# C210_0005_NINA_Module.net
KiCad netlist of a schematic drawn in Altium Designer
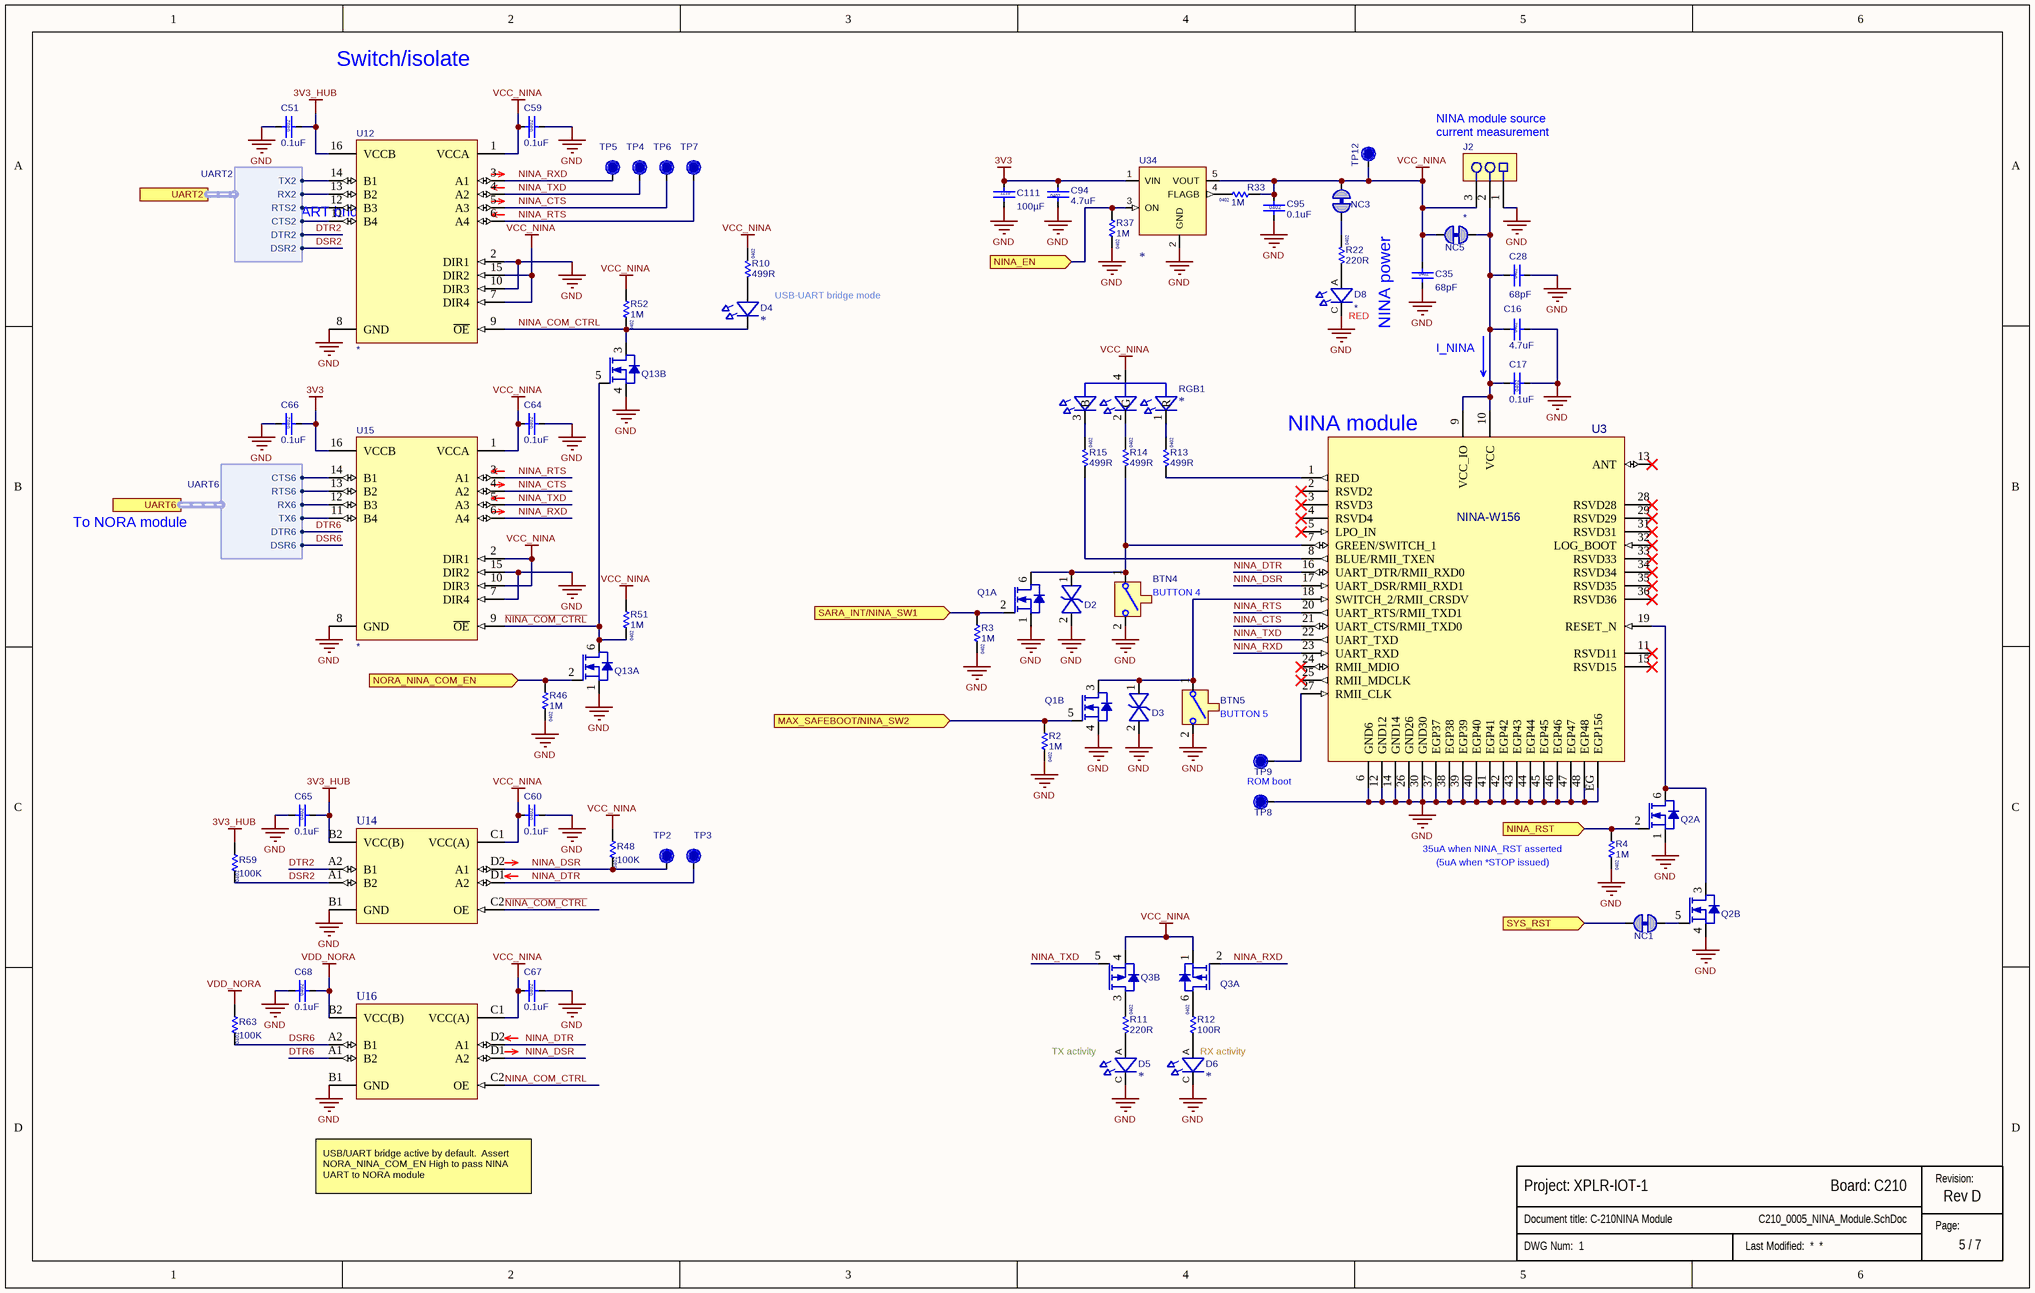
[diagram p0: C210_0005_NINA_Module.SchDoc]

(export (version "E")
  (design (tool "Eeschema 10.0.6"))
  (components
    (comp (ref "BTN4")
      (value "135-00007")
      (footprint "B3U-1000P")
      (description "Button, Momentary SPST-NO, 0.05A, 12V, 3mm x 2.5mm")
      (fields (field (name "VOLTAGE") "12VDC"))
      (libsource (lib "Arena_Parts_DB_Lib") (part "SW_SPST"))
    )
    (comp (ref "BTN5")
      (value "135-00007")
      (footprint "B3U-1000P")
      (description "Button, Momentary SPST-NO, 0.05A, 12V, 3mm x 2.5mm")
      (fields (field (name "VOLTAGE") "12VDC"))
      (libsource (lib "Arena_Parts_DB_Lib") (part "SW_SPST"))
    )
    (comp (ref "C16")
      (value "4.7uF")
      (footprint "Cap 0402 HD")
      (description "Cap, Ceramic 4.7uF 10V 20% X5R 0402")
      (fields
        (field (name "SIZE") "0402")
        (field (name "PART NUMBER") "120-00020")
        (field (name "TOLERANCE") "+/- 20%")
      )
      (libsource (lib "Arena_Parts_DB_Lib") (part "Cap Chip"))
    )
    (comp (ref "C17")
      (value "0.1uF")
      (footprint "Cap 0402 HD")
      (description "Cap, Ceramic 0.1uF 10V 10% X5R 0402")
      (fields
        (field (name "SIZE") "0402")
        (field (name "PART NUMBER") "120-00016")
        (field (name "MANUFACTURER") "Murata Electronics North America")
      )
      (libsource (lib "Arena_Parts_DB_Lib") (part "Cap Chip"))
    )
    (comp (ref "C28")
      (value "68pF")
      (footprint "Cap 0402 HD")
      (description "Cap, Ceramic, 68pF, 50V, 1%, NP0, 0402")
      (fields
        (field (name "SIZE") "0402")
        (field (name "PART NUMBER") "120-00047")
        (field (name "TOLERANCE") "+/- 1%")
      )
      (libsource (lib "Arena_Parts_DB_Lib") (part "Cap Chip"))
    )
    (comp (ref "C35")
      (value "68pF")
      (footprint "Cap 0402 HD")
      (description "Cap, Ceramic, 68pF, 50V, 1%, NP0, 0402")
      (fields
        (field (name "SIZE") "0402")
        (field (name "PART NUMBER") "120-00047")
        (field (name "TOLERANCE") "+/- 1%")
      )
      (libsource (lib "Arena_Parts_DB_Lib") (part "Cap Chip"))
    )
    (comp (ref "C51")
      (value "0.1uF")
      (footprint "Cap 0402 HD")
      (description "Cap, Ceramic 0.1uF 10V 10% X5R 0402")
      (fields
        (field (name "SIZE") "0402")
        (field (name "PART NUMBER") "120-00016")
        (field (name "MANUFACTURER") "Murata Electronics North America")
      )
      (libsource (lib "Arena_Parts_DB_Lib") (part "Cap Chip"))
    )
    (comp (ref "C59")
      (value "0.1uF")
      (footprint "Cap 0402 HD")
      (description "Cap, Ceramic 0.1uF 10V 10% X5R 0402")
      (fields
        (field (name "SIZE") "0402")
        (field (name "PART NUMBER") "120-00016")
        (field (name "MANUFACTURER") "Murata Electronics North America")
      )
      (libsource (lib "Arena_Parts_DB_Lib") (part "Cap Chip"))
    )
    (comp (ref "C60")
      (value "0.1uF")
      (footprint "Cap 0402 HD")
      (description "Cap, Ceramic 0.1uF 10V 10% X5R 0402")
      (fields
        (field (name "SIZE") "0402")
        (field (name "PART NUMBER") "120-00016")
        (field (name "MANUFACTURER") "Murata Electronics North America")
      )
      (libsource (lib "Arena_Parts_DB_Lib") (part "Cap Chip"))
    )
    (comp (ref "C64")
      (value "0.1uF")
      (footprint "Cap 0402 HD")
      (description "Cap, Ceramic 0.1uF 10V 10% X5R 0402")
      (fields
        (field (name "SIZE") "0402")
        (field (name "PART NUMBER") "120-00016")
        (field (name "MANUFACTURER") "Murata Electronics North America")
      )
      (libsource (lib "Arena_Parts_DB_Lib") (part "Cap Chip"))
    )
    (comp (ref "C65")
      (value "0.1uF")
      (footprint "Cap 0402 HD")
      (description "Cap, Ceramic 0.1uF 10V 10% X5R 0402")
      (fields
        (field (name "SIZE") "0402")
        (field (name "PART NUMBER") "120-00016")
        (field (name "MANUFACTURER") "Murata Electronics North America")
      )
      (libsource (lib "Arena_Parts_DB_Lib") (part "Cap Chip"))
    )
    (comp (ref "C66")
      (value "0.1uF")
      (footprint "Cap 0402 HD")
      (description "Cap, Ceramic 0.1uF 10V 10% X5R 0402")
      (fields
        (field (name "SIZE") "0402")
        (field (name "PART NUMBER") "120-00016")
        (field (name "MANUFACTURER") "Murata Electronics North America")
      )
      (libsource (lib "Arena_Parts_DB_Lib") (part "Cap Chip"))
    )
    (comp (ref "C67")
      (value "0.1uF")
      (footprint "Cap 0402 HD")
      (description "Cap, Ceramic 0.1uF 10V 10% X5R 0402")
      (fields
        (field (name "SIZE") "0402")
        (field (name "PART NUMBER") "120-00016")
        (field (name "MANUFACTURER") "Murata Electronics North America")
      )
      (libsource (lib "Arena_Parts_DB_Lib") (part "Cap Chip"))
    )
    (comp (ref "C68")
      (value "0.1uF")
      (footprint "Cap 0402 HD")
      (description "Cap, Ceramic 0.1uF 10V 10% X5R 0402")
      (fields
        (field (name "SIZE") "0402")
        (field (name "PART NUMBER") "120-00016")
        (field (name "MANUFACTURER") "Murata Electronics North America")
      )
      (libsource (lib "Arena_Parts_DB_Lib") (part "Cap Chip"))
    )
    (comp (ref "C94")
      (value "4.7uF")
      (footprint "Cap 0402 HD")
      (description "Cap, Ceramic 4.7uF 10V 20% X5R 0402")
      (fields
        (field (name "SIZE") "0402")
        (field (name "PART NUMBER") "120-00020")
        (field (name "TOLERANCE") "+/- 20%")
      )
      (libsource (lib "Arena_Parts_DB_Lib") (part "Cap Chip"))
    )
    (comp (ref "C95")
      (value "0.1uF")
      (footprint "Cap 0402 HD")
      (description "Cap, Ceramic 0.1uF 10V 10% X5R 0402")
      (fields
        (field (name "SIZE") "0402")
        (field (name "PART NUMBER") "120-00016")
        (field (name "MANUFACTURER") "Murata Electronics North America")
      )
      (libsource (lib "Arena_Parts_DB_Lib") (part "Cap Chip"))
    )
    (comp (ref "C111")
      (value "100µF")
      (footprint "Cap 1210")
      (description "100µF ±20% 10V Ceramic Capacitor X5R 1210 (3225 Metric)")
      (fields
        (field (name "SIZE") "1210")
        (field (name "PART NUMBER") "120-00223")
        (field (name "TOLERANCE") "+/- 20%")
      )
      (libsource (lib "Arena_Parts_DB_Lib") (part "Cap Chip"))
    )
    (comp (ref "D2")
      (value "110-00041")
      (footprint "SOD-523_ALT")
      (description "Diode TVS 5VWM BiDIR SOD523")
      (fields (field (name "VOLTAGE") "5VWM"))
      (libsource (lib "Arena_Parts_DB_Lib") (part "Diode_TVS"))
    )
    (comp (ref "D3")
      (value "110-00041")
      (footprint "SOD-523_ALT")
      (description "Diode TVS 5VWM BiDIR SOD523")
      (fields (field (name "VOLTAGE") "5VWM"))
      (libsource (lib "Arena_Parts_DB_Lib") (part "Diode_TVS"))
    )
    (comp (ref "D4")
      (value "115-00023")
      (footprint "LED-0603")
      (description "LED BLUE DIFFUSED 0603 SMD")
      (fields (field (name "COLOR") "*") (field (name "VOLTAGE") "None"))
      (libsource (lib "Arena_Parts_DB_Lib") (part "LED_BASE"))
    )
    (comp (ref "D5")
      (value "115-00019")
      (footprint "LTST-C190KGKT")
      (description "DIODE, LED, SMT, GREEN, CLEAR LENS, 2.0V 20mA, 0603")
      (fields (field (name "VOLTAGE") "2.0V") (field (name "COLOR") "*"))
      (libsource (lib "LTST-C190KGKT") (part "LTST-C190KGKT"))
    )
    (comp (ref "D6")
      (value "LTST-C190YKT")
      (footprint "LTST-C190YKT")
      (description "DIODE, LED, SMT, YELLOW, CLEAR LENS, 2.1V 10mA, 0603")
      (fields (field (name "VOLTAGE") "2.1V") (field (name "COLOR") "*"))
      (libsource (lib "LTST-C190YKT") (part "LTST-C190YKT"))
    )
    (comp (ref "D8")
      (value "LTST-C190EKT")
      (footprint "LTST-C190EKT")
      (description "DIODE, LED, SMT, Red, CLEAR LENS, 2.0V 10mA, 0603")
      (fields (field (name "VOLTAGE") "2.0V") (field (name "COLOR") "*"))
      (libsource (lib "LTST-C190EKT") (part "LTST-C190EKT"))
    )
    (comp (ref "J2")
      (value "130-00105")
      (footprint "HDR-0.1P-3Pin-1Row-SMT")
      (description "Header, 0.100\" Pitch, 3 Pin, Vertical SMT, Black")
      (fields (field (name "MANUFACTURER P/N") "*") (field (name "VOLTAGE") "None"))
      (libsource (lib "Arena_Parts_DB_Lib") (part "CON-3Pin_1Row"))
    )
    (comp (ref "NC1")
      (value "Solderbridge-ShortDNP")
      (footprint "Solderbridge-Short")
      (description "Solderbridge-Short")
      (fields (field (name "ADDED BY") "Paul B"))
      (libsource (lib "PCB_Misc") (part "Solderbridge-Short"))
    )
    (comp (ref "NC3")
      (value "Solderbridge-ShortDNP")
      (footprint "Solderbridge-Short")
      (description "Solderbridge-Short")
      (fields (field (name "ADDED BY") "Paul B"))
      (libsource (lib "") (part "Solderbridge-Short_1"))
    )
    (comp (ref "NC5")
      (value "Solderbridge-ShortDNP")
      (footprint "Solderbridge-Short")
      (description "Solderbridge-Short")
      (fields (field (name "ADDED BY") "Paul B"))
      (libsource (lib "PCB_Misc") (part "Solderbridge-Short"))
    )
    (comp (ref "Q1")
      (value "140-00016")
      (footprint "SOT-563")
      (description "MOSFET 2N-CH 20V 0.8A, SOT-563")
      (fields (field (name "VOLTAGE") "20V"))
      (libsource (lib "Arena_Parts_DB_Lib") (part "MOSFET-N-Dual"))
    )
    (comp (ref "Q2")
      (value "140-00016")
      (footprint "SOT-563")
      (description "MOSFET 2N-CH 20V 0.8A, SOT-563")
      (fields (field (name "VOLTAGE") "20V"))
      (libsource (lib "Arena_Parts_DB_Lib") (part "MOSFET-N-Dual"))
    )
    (comp (ref "Q3")
      (value "FDY2000PZ")
      (footprint "FDY2000PZ")
      (description "MOSFET DUAL P-CH 20V SOT-563, -350mA")
      (fields (field (name "VOLTAGE") "20V"))
      (libsource (lib "FDY2000PZ") (part "MOSFET-Dual-P_Chan"))
    )
    (comp (ref "Q13")
      (value "140-00016")
      (footprint "SOT-563")
      (description "MOSFET 2N-CH 20V 0.8A, SOT-563")
      (fields (field (name "VOLTAGE") "20V"))
      (libsource (lib "Arena_Parts_DB_Lib") (part "MOSFET-N-Dual"))
    )
    (comp (ref "R2")
      (value "1M")
      (footprint "RES 0402 HD")
      (description "Resistor 1M ohm 1%, 1/16W, 0402")
      (fields
        (field (name "SIZE") "0402")
        (field (name "PART NUMBER") "180-00054")
        (field (name "POWER") "1/16W")
      )
      (libsource (lib "Arena_Parts_DB_Lib") (part "Res sm"))
    )
    (comp (ref "R3")
      (value "1M")
      (footprint "RES 0402 HD")
      (description "Resistor 1M ohm 1%, 1/16W, 0402")
      (fields
        (field (name "SIZE") "0402")
        (field (name "PART NUMBER") "180-00054")
        (field (name "POWER") "1/16W")
      )
      (libsource (lib "Arena_Parts_DB_Lib") (part "Res sm"))
    )
    (comp (ref "R4")
      (value "1M")
      (footprint "RES 0402 HD")
      (description "Resistor 1M ohm 1%, 1/16W, 0402")
      (fields
        (field (name "SIZE") "0402")
        (field (name "PART NUMBER") "180-00054")
        (field (name "POWER") "1/16W")
      )
      (libsource (lib "Arena_Parts_DB_Lib") (part "Res sm"))
    )
    (comp (ref "R10")
      (value "499R")
      (footprint "RES 0402 HD")
      (description "Resistor, 499ohm, 1%, 1/16W, 0402")
      (fields
        (field (name "SIZE") "0402")
        (field (name "PART NUMBER") "180-00031")
        (field (name "MANUFACTURER") "Rohm Semiconductor")
      )
      (libsource (lib "Arena_Parts_DB_Lib") (part "Res sm"))
    )
    (comp (ref "R11")
      (value "220R")
      (footprint "RES 0402 HD")
      (description "Resistor, 220ohm, 5%, 1/16W, 0402.")
      (fields
        (field (name "SIZE") "0402")
        (field (name "PART NUMBER") "180-00098")
        (field (name "MANUFACTURER") "Panasonic Electronic Components")
      )
      (libsource (lib "Arena_Parts_DB_Lib") (part "Res sm"))
    )
    (comp (ref "R12")
      (value "100R")
      (footprint "RES 0402 HD")
      (description "Resistor, 100ohm, 1%, 1/16W, 0402.")
      (fields
        (field (name "SIZE") "0402")
        (field (name "PART NUMBER") "180-00051")
        (field (name "POWER") "1/16W")
      )
      (libsource (lib "Arena_Parts_DB_Lib") (part "Res sm"))
    )
    (comp (ref "R13")
      (value "499R")
      (footprint "RES 0402 HD")
      (description "Resistor, 499ohm, 1%, 1/16W, 0402")
      (fields
        (field (name "SIZE") "0402")
        (field (name "PART NUMBER") "180-00031")
        (field (name "MANUFACTURER") "Rohm Semiconductor")
      )
      (libsource (lib "Arena_Parts_DB_Lib") (part "Res sm"))
    )
    (comp (ref "R14")
      (value "499R")
      (footprint "RES 0402 HD")
      (description "Resistor, 499ohm, 1%, 1/16W, 0402")
      (fields
        (field (name "SIZE") "0402")
        (field (name "PART NUMBER") "180-00031")
        (field (name "MANUFACTURER") "Rohm Semiconductor")
      )
      (libsource (lib "Arena_Parts_DB_Lib") (part "Res sm"))
    )
    (comp (ref "R15")
      (value "499R")
      (footprint "RES 0402 HD")
      (description "Resistor, 499ohm, 1%, 1/16W, 0402")
      (fields
        (field (name "SIZE") "0402")
        (field (name "PART NUMBER") "180-00031")
        (field (name "MANUFACTURER") "Rohm Semiconductor")
      )
      (libsource (lib "Arena_Parts_DB_Lib") (part "Res sm"))
    )
    (comp (ref "R22")
      (value "220R")
      (footprint "RES 0402 HD")
      (description "Resistor, 220ohm, 5%, 1/16W, 0402.")
      (fields
        (field (name "SIZE") "0402")
        (field (name "PART NUMBER") "180-00098")
        (field (name "MANUFACTURER") "Panasonic Electronic Components")
      )
      (libsource (lib "Arena_Parts_DB_Lib") (part "Res sm"))
    )
    (comp (ref "R33")
      (value "1M")
      (footprint "RES 0402 HD")
      (description "Resistor 1M ohm 1%, 1/16W, 0402")
      (fields
        (field (name "SIZE") "0402")
        (field (name "PART NUMBER") "180-00054")
        (field (name "POWER") "1/16W")
      )
      (libsource (lib "Arena_Parts_DB_Lib") (part "Res sm"))
    )
    (comp (ref "R37")
      (value "1M")
      (footprint "RES 0402 HD")
      (description "Resistor 1M ohm 1%, 1/16W, 0402")
      (fields
        (field (name "SIZE") "0402")
        (field (name "PART NUMBER") "180-00054")
        (field (name "POWER") "1/16W")
      )
      (libsource (lib "Arena_Parts_DB_Lib") (part "Res sm"))
    )
    (comp (ref "R46")
      (value "1M")
      (footprint "RES 0402 HD")
      (description "Resistor 1M ohm 1%, 1/16W, 0402")
      (fields
        (field (name "SIZE") "0402")
        (field (name "PART NUMBER") "180-00054")
        (field (name "POWER") "1/16W")
      )
      (libsource (lib "Arena_Parts_DB_Lib") (part "Res sm"))
    )
    (comp (ref "R48")
      (value "100K")
      (footprint "RES 0402 HD")
      (description "Resistor 100K ohm 1% 1/16W, 0402")
      (fields
        (field (name "SIZE") "0402")
        (field (name "PART NUMBER") "180-00093")
        (field (name "POWER") "1/16W")
      )
      (libsource (lib "Arena_Parts_DB_Lib") (part "Res sm"))
    )
    (comp (ref "R51")
      (value "1M")
      (footprint "RES 0402 HD")
      (description "Resistor 1M ohm 1%, 1/16W, 0402")
      (fields
        (field (name "SIZE") "0402")
        (field (name "PART NUMBER") "180-00054")
        (field (name "POWER") "1/16W")
      )
      (libsource (lib "Arena_Parts_DB_Lib") (part "Res sm"))
    )
    (comp (ref "R52")
      (value "1M")
      (footprint "RES 0402 HD")
      (description "Resistor 1M ohm 1%, 1/16W, 0402")
      (fields
        (field (name "SIZE") "0402")
        (field (name "PART NUMBER") "180-00054")
        (field (name "POWER") "1/16W")
      )
      (libsource (lib "Arena_Parts_DB_Lib") (part "Res sm"))
    )
    (comp (ref "R59")
      (value "100K")
      (footprint "RES 0402 HD")
      (description "Resistor 100K ohm 1% 1/16W, 0402")
      (fields
        (field (name "SIZE") "0402")
        (field (name "PART NUMBER") "180-00093")
        (field (name "POWER") "1/16W")
      )
      (libsource (lib "Arena_Parts_DB_Lib") (part "Res sm"))
    )
    (comp (ref "R63")
      (value "100K")
      (footprint "RES 0402 HD")
      (description "Resistor 100K ohm 1% 1/16W, 0402")
      (fields
        (field (name "SIZE") "0402")
        (field (name "PART NUMBER") "180-00093")
        (field (name "POWER") "1/16W")
      )
      (libsource (lib "Arena_Parts_DB_Lib") (part "Res sm"))
    )
    (comp (ref "RGB1")
      (value "115-00026")
      (footprint "LED_1616")
      (description "LED RGB SMT 0606")
      (fields (field (name "COLOR") "*") (field (name "VOLTAGE") "None"))
      (libsource (lib "Arena_Parts_DB_Lib") (part "LED_RGB_CA_4"))
    )
    (comp (ref "TP2")
      (value "TP")
      (footprint "TP12R")
      (description "Testpoint, Round 1.0mm Dia")
      (fields
        (field (name "PART NUMBER") "TP10R")
        (field (name "ADDED BY") "Jeremy D")
        (field (name "CHECKED BY") "Paul B")
      )
      (libsource (lib "PCB_Misc") (part "TP_R"))
    )
    (comp (ref "TP3")
      (value "TP")
      (footprint "TP12R")
      (description "Testpoint, Round 1.0mm Dia")
      (fields
        (field (name "PART NUMBER") "TP10R")
        (field (name "ADDED BY") "Jeremy D")
        (field (name "CHECKED BY") "Paul B")
      )
      (libsource (lib "PCB_Misc") (part "TP_R"))
    )
    (comp (ref "TP4")
      (value "TP")
      (footprint "TP12R")
      (description "Testpoint, Round 1.0mm Dia")
      (fields
        (field (name "PART NUMBER") "TP10R")
        (field (name "ADDED BY") "Jeremy D")
        (field (name "CHECKED BY") "Paul B")
      )
      (libsource (lib "PCB_Misc") (part "TP_R"))
    )
    (comp (ref "TP5")
      (value "TP")
      (footprint "TP12R")
      (description "Testpoint, Round 1.0mm Dia")
      (fields
        (field (name "PART NUMBER") "TP10R")
        (field (name "ADDED BY") "Jeremy D")
        (field (name "CHECKED BY") "Paul B")
      )
      (libsource (lib "PCB_Misc") (part "TP_R"))
    )
    (comp (ref "TP6")
      (value "TP")
      (footprint "TP12R")
      (description "Testpoint, Round 1.0mm Dia")
      (fields
        (field (name "PART NUMBER") "TP10R")
        (field (name "ADDED BY") "Jeremy D")
        (field (name "CHECKED BY") "Paul B")
      )
      (libsource (lib "PCB_Misc") (part "TP_R"))
    )
    (comp (ref "TP7")
      (value "TP")
      (footprint "TP12R")
      (description "Testpoint, Round 1.0mm Dia")
      (fields
        (field (name "PART NUMBER") "TP10R")
        (field (name "ADDED BY") "Jeremy D")
        (field (name "CHECKED BY") "Paul B")
      )
      (libsource (lib "PCB_Misc") (part "TP_R"))
    )
    (comp (ref "TP8")
      (value "TP")
      (footprint "TP12R")
      (description "Testpoint, Round 1.0mm Dia")
      (fields
        (field (name "PART NUMBER") "TP10R")
        (field (name "ADDED BY") "Jeremy D")
        (field (name "CHECKED BY") "Paul B")
      )
      (libsource (lib "PCB_Misc") (part "TP_R"))
    )
    (comp (ref "TP9")
      (value "TP")
      (footprint "TP12R")
      (description "Testpoint, Round 1.0mm Dia")
      (fields
        (field (name "PART NUMBER") "TP10R")
        (field (name "ADDED BY") "Jeremy D")
        (field (name "CHECKED BY") "Paul B")
      )
      (libsource (lib "PCB_Misc") (part "TP_R"))
    )
    (comp (ref "TP12")
      (value "TP")
      (footprint "TP12R")
      (description "Testpoint, Round 1.0mm Dia")
      (fields
        (field (name "PART NUMBER") "TP10R")
        (field (name "ADDED BY") "Jeremy D")
        (field (name "CHECKED BY") "Paul B")
      )
      (libsource (lib "PCB_Misc") (part "TP_R"))
    )
    (comp (ref "U3")
      (value "NINA-W156")
      (footprint "NINA_LGA48R_1400X1000X223_PCB")
      (description "u-blox NINA-W156 WiFi, Bluetooth dual-mode module")
      (fields (field (name "MANUFACTURER") "u-blox"))
      (libsource (lib "ubloxLib") (part "NINA-W156"))
    )
    (comp (ref "U12")
      (value "225-00011")
      (footprint "QFN0.5P2x6-16Pin_W-Pad")
      (description "Voltage Level Translator Bidirectional 1 Circuit 4 Channel 380Mbps 16-DHVQFN (2.5x3.5)")
      (fields (field (name "MANUFACTURER P/N") "*") (field (name "VOLTAGE") "3.6V"))
      (libsource (lib "Arena_Parts_DB_Lib") (part "74AVC4TD245"))
    )
    (comp (ref "U14")
      (value "TXS0102YZP")
      (footprint "TXS0102YZP")
      (description "IC, SMT, LEVEL TRANSLATOR, DUAL, BIDIRECTIONAL, DSBGA-8 1.9mmX0.9mm")
      (libsource (lib "TXS0102YZP") (part "TXS0102YZP"))
    )
    (comp (ref "U15")
      (value "225-00011")
      (footprint "QFN0.5P2x6-16Pin_W-Pad")
      (description "Voltage Level Translator Bidirectional 1 Circuit 4 Channel 380Mbps 16-DHVQFN (2.5x3.5)")
      (fields (field (name "MANUFACTURER P/N") "*") (field (name "VOLTAGE") "3.6V"))
      (libsource (lib "Arena_Parts_DB_Lib") (part "74AVC4TD245"))
    )
    (comp (ref "U16")
      (value "TXS0102YZP")
      (footprint "TXS0102YZP")
      (description "IC, SMT, LEVEL TRANSLATOR, DUAL, BIDIRECTIONAL, DSBGA-8 1.9mmX0.9mm")
      (libsource (lib "TXS0102YZP") (part "TXS0102YZP"))
    )
    (comp (ref "U34")
      (value "~")
      (footprint "SOT-23-5_2")
      (description "Load Switch, 400mA, 1.8-5.5V, Active High Enable, SOT-23-5")
      (fields (field (name "VOLTAGE") "5.5V") (field (name "MANUFACTURER P/N") "*"))
      (libsource (lib "FPF2104") (part "FPF2104"))
    )
  )
  (nets
    (net (code "3") (name "/CTS2") (class "Default")
      (node (ref "U12") (pin "11") (pinfunction "B4_11") (pintype "bidirectional"))
    )
    (net (code "4") (name "/CTS6") (class "Default")
      (node (ref "U15") (pin "14") (pinfunction "B1_14") (pintype "bidirectional"))
    )
    (net (code "5") (name "/DSR2") (class "Default")
      (node (ref "R59") (pin "2") (pinfunction "2_2") (pintype "passive"))
      (node (ref "U14") (pin "A1") (pinfunction "B2_A1") (pintype "bidirectional"))
    )
    (net (code "6") (name "/DSR6") (class "Default")
      (node (ref "R63") (pin "2") (pinfunction "2_2") (pintype "passive"))
      (node (ref "U16") (pin "A2") (pinfunction "B1_A2") (pintype "bidirectional"))
    )
    (net (code "7") (name "/DTR2") (class "Default")
      (node (ref "U14") (pin "A2") (pinfunction "B1_A2") (pintype "bidirectional"))
    )
    (net (code "8") (name "/DTR6") (class "Default")
      (node (ref "U16") (pin "A1") (pinfunction "B2_A1") (pintype "bidirectional"))
    )
    (net (code "9") (name "/MAX_SAFEBOOT{slash}NINA_SW2") (class "Default")
      (node (ref "Q1") (pin "5") (pinfunction "G2_5") (pintype "passive"))
      (node (ref "R2") (pin "1") (pinfunction "1_1") (pintype "passive"))
    )
    (net (code "10") (name "/NINA_COM_CTRL") (class "Default")
      (node (ref "D4") (pin "1") (pinfunction "C_1") (pintype "passive"))
      (node (ref "Q13") (pin "3") (pinfunction "D2_3") (pintype "passive"))
      (node (ref "R52") (pin "2") (pinfunction "2_2") (pintype "passive"))
      (node (ref "U12") (pin "9") (pinfunction "~{OE}_9") (pintype "input"))
      (node (ref "U16") (pin "C2") (pinfunction "OE_C2") (pintype "input"))
    )
    (net (code "11") (name "/NINA_CTS") (class "Default")
      (node (ref "TP6") (pin "1") (pintype "passive"))
      (node (ref "U12") (pin "5") (pinfunction "A3_5") (pintype "bidirectional"))
      (node (ref "U15") (pin "4") (pinfunction "A2_4") (pintype "bidirectional"))
      (node (ref "U3") (pin "21") (pinfunction "UART_CTS/RMII_TXD0_21") (pintype "bidirectional"))
    )
    (net (code "12") (name "/NINA_DSR") (class "Default")
      (node (ref "R48") (pin "2") (pinfunction "2_2") (pintype "passive"))
      (node (ref "TP2") (pin "1") (pintype "passive"))
      (node (ref "U14") (pin "D2") (pinfunction "A1_D2") (pintype "bidirectional"))
      (node (ref "U16") (pin "D1") (pinfunction "A2_D1") (pintype "bidirectional"))
      (node (ref "U3") (pin "17") (pinfunction "UART_DSR/RMII_RXD1_17") (pintype "input"))
    )
    (net (code "13") (name "/NINA_DTR") (class "Default")
      (node (ref "TP3") (pin "1") (pintype "passive"))
      (node (ref "U14") (pin "D1") (pinfunction "A2_D1") (pintype "bidirectional"))
      (node (ref "U16") (pin "D2") (pinfunction "A1_D2") (pintype "bidirectional"))
      (node (ref "U3") (pin "16") (pinfunction "UART_DTR/RMII_RXD0_16") (pintype "bidirectional"))
    )
    (net (code "14") (name "/NINA_EN") (class "Default")
      (node (ref "R37") (pin "1") (pinfunction "1_1") (pintype "passive"))
      (node (ref "U34") (pin "3") (pinfunction "ON_3") (pintype "input"))
    )
    (net (code "15") (name "/NINA_RST") (class "Default")
      (node (ref "Q2") (pin "2") (pinfunction "G1_2") (pintype "passive"))
      (node (ref "R4") (pin "1") (pinfunction "1_1") (pintype "passive"))
    )
    (net (code "16") (name "/NINA_RTS") (class "Default")
      (node (ref "TP7") (pin "1") (pintype "passive"))
      (node (ref "U12") (pin "6") (pinfunction "A4_6") (pintype "bidirectional"))
      (node (ref "U15") (pin "3") (pinfunction "A1_3") (pintype "bidirectional"))
      (node (ref "U3") (pin "20") (pinfunction "UART_RTS/RMII_TXD1_20") (pintype "output"))
    )
    (net (code "17") (name "/NINA_RXD") (class "Default")
      (node (ref "Q3") (pin "2") (pinfunction "G1_2") (pintype "passive"))
      (node (ref "TP5") (pin "1") (pintype "passive"))
      (node (ref "U12") (pin "3") (pinfunction "A1_3") (pintype "bidirectional"))
      (node (ref "U15") (pin "6") (pinfunction "A4_6") (pintype "bidirectional"))
      (node (ref "U3") (pin "23") (pinfunction "UART_RXD_23") (pintype "input"))
    )
    (net (code "18") (name "/NINA_TXD") (class "Default")
      (node (ref "Q3") (pin "5") (pinfunction "G2_5") (pintype "passive"))
      (node (ref "TP4") (pin "1") (pintype "passive"))
      (node (ref "U12") (pin "4") (pinfunction "A2_4") (pintype "bidirectional"))
      (node (ref "U15") (pin "5") (pinfunction "A3_5") (pintype "bidirectional"))
      (node (ref "U3") (pin "22") (pinfunction "UART_TXD_22") (pintype "output"))
    )
    (net (code "19") (name "/NORA_NINA_COM_EN") (class "Default")
      (node (ref "Q13") (pin "2") (pinfunction "G1_2") (pintype "passive"))
      (node (ref "R46") (pin "1") (pinfunction "1_1") (pintype "passive"))
    )
    (net (code "20") (name "/RTS2") (class "Default")
      (node (ref "U12") (pin "12") (pinfunction "B3_12") (pintype "bidirectional"))
    )
    (net (code "21") (name "/RTS6") (class "Default")
      (node (ref "U15") (pin "13") (pinfunction "B2_13") (pintype "bidirectional"))
    )
    (net (code "22") (name "/RX2") (class "Default")
      (node (ref "U12") (pin "13") (pinfunction "B2_13") (pintype "bidirectional"))
    )
    (net (code "23") (name "/RX6") (class "Default")
      (node (ref "U15") (pin "12") (pinfunction "B3_12") (pintype "bidirectional"))
    )
    (net (code "24") (name "/SARA_INT{slash}NINA_SW1") (class "Default")
      (node (ref "Q1") (pin "2") (pinfunction "G1_2") (pintype "passive"))
      (node (ref "R3") (pin "1") (pinfunction "1_1") (pintype "passive"))
    )
    (net (code "25") (name "/SYS_RST") (class "Default")
      (node (ref "NC1") (pin "2") (pinfunction "2_2") (pintype "passive"))
    )
    (net (code "26") (name "/TX2") (class "Default")
      (node (ref "U12") (pin "14") (pinfunction "B1_14") (pintype "bidirectional"))
    )
    (net (code "27") (name "/TX6") (class "Default")
      (node (ref "U15") (pin "11") (pinfunction "B4_11") (pintype "bidirectional"))
    )
    (net (code "30") (name "/~{NINA_COM_CTRL}") (class "Default")
      (node (ref "Q13") (pin "5") (pinfunction "G2_5") (pintype "passive"))
      (node (ref "Q13") (pin "6") (pinfunction "D1_6") (pintype "passive"))
      (node (ref "R51") (pin "2") (pinfunction "2_2") (pintype "passive"))
      (node (ref "U14") (pin "C2") (pinfunction "OE_C2") (pintype "input"))
      (node (ref "U15") (pin "9") (pinfunction "~{OE}_9") (pintype "input"))
    )
    (net (code "31") (name "3V3") (class "Default")
      (node (ref "C111") (pin "1") (pinfunction "1_1") (pintype "passive"))
      (node (ref "C66") (pin "2") (pinfunction "2_2") (pintype "passive"))
      (node (ref "C94") (pin "2") (pinfunction "2_2") (pintype "passive"))
      (node (ref "U15") (pin "16") (pinfunction "VCCB_16") (pintype "power_in"))
      (node (ref "U34") (pin "1") (pinfunction "VIN_1") (pintype "power_in"))
    )
    (net (code "32") (name "3V3_HUB") (class "Default")
      (node (ref "C51") (pin "2") (pinfunction "2_2") (pintype "passive"))
      (node (ref "C65") (pin "2") (pinfunction "2_2") (pintype "passive"))
      (node (ref "R59") (pin "1") (pinfunction "1_1") (pintype "passive"))
      (node (ref "U12") (pin "16") (pinfunction "VCCB_16") (pintype "power_in"))
      (node (ref "U14") (pin "B2") (pinfunction "VCC(B)_B2") (pintype "power_in"))
    )
    (net (code "33") (name "GND") (class "Default")
      (node (ref "BTN4") (pin "2") (pinfunction "2_2") (pintype "passive"))
      (node (ref "BTN5") (pin "2") (pinfunction "2_2") (pintype "passive"))
      (node (ref "C111") (pin "2") (pinfunction "2_2") (pintype "passive"))
      (node (ref "C16") (pin "2") (pinfunction "2_2") (pintype "passive"))
      (node (ref "C17") (pin "1") (pinfunction "1_1") (pintype "passive"))
      (node (ref "C28") (pin "2") (pinfunction "2_2") (pintype "passive"))
      (node (ref "C35") (pin "2") (pinfunction "2_2") (pintype "passive"))
      (node (ref "C51") (pin "1") (pinfunction "1_1") (pintype "passive"))
      (node (ref "C59") (pin "2") (pinfunction "2_2") (pintype "passive"))
      (node (ref "C60") (pin "2") (pinfunction "2_2") (pintype "passive"))
      (node (ref "C64") (pin "2") (pinfunction "2_2") (pintype "passive"))
      (node (ref "C65") (pin "1") (pinfunction "1_1") (pintype "passive"))
      (node (ref "C66") (pin "1") (pinfunction "1_1") (pintype "passive"))
      (node (ref "C67") (pin "2") (pinfunction "2_2") (pintype "passive"))
      (node (ref "C68") (pin "1") (pinfunction "1_1") (pintype "passive"))
      (node (ref "C94") (pin "1") (pinfunction "1_1") (pintype "passive"))
      (node (ref "C95") (pin "2") (pinfunction "2_2") (pintype "passive"))
      (node (ref "D2") (pin "2") (pintype "passive"))
      (node (ref "D3") (pin "2") (pintype "passive"))
      (node (ref "D5") (pin "C") (pinfunction "Cathode_C") (pintype "passive"))
      (node (ref "D6") (pin "C") (pinfunction "Cathode_C") (pintype "passive"))
      (node (ref "D8") (pin "C") (pinfunction "Cathode_C") (pintype "passive"))
      (node (ref "J2") (pin "1") (pinfunction "1_1") (pintype "passive"))
      (node (ref "Q1") (pin "1") (pinfunction "S1_1") (pintype "passive"))
      (node (ref "Q1") (pin "4") (pinfunction "S2_4") (pintype "passive"))
      (node (ref "Q13") (pin "1") (pinfunction "S1_1") (pintype "passive"))
      (node (ref "Q13") (pin "4") (pinfunction "S2_4") (pintype "passive"))
      (node (ref "Q2") (pin "1") (pinfunction "S1_1") (pintype "passive"))
      (node (ref "Q2") (pin "4") (pinfunction "S2_4") (pintype "passive"))
      (node (ref "R2") (pin "2") (pinfunction "2_2") (pintype "passive"))
      (node (ref "R3") (pin "2") (pinfunction "2_2") (pintype "passive"))
      (node (ref "R37") (pin "2") (pinfunction "2_2") (pintype "passive"))
      (node (ref "R4") (pin "2") (pinfunction "2_2") (pintype "passive"))
      (node (ref "R46") (pin "2") (pinfunction "2_2") (pintype "passive"))
      (node (ref "TP8") (pin "1") (pintype "passive"))
      (node (ref "U12") (pin "10") (pinfunction "DIR3_10") (pintype "input"))
      (node (ref "U12") (pin "2") (pinfunction "DIR1_2") (pintype "input"))
      (node (ref "U12") (pin "8") (pinfunction "GND_8") (pintype "power_in"))
      (node (ref "U14") (pin "B1") (pinfunction "GND_B1") (pintype "power_in"))
      (node (ref "U15") (pin "15") (pinfunction "DIR2_15") (pintype "input"))
      (node (ref "U15") (pin "7") (pinfunction "DIR4_7") (pintype "input"))
      (node (ref "U15") (pin "8") (pinfunction "GND_8") (pintype "power_in"))
      (node (ref "U16") (pin "B1") (pinfunction "GND_B1") (pintype "power_in"))
      (node (ref "U3") (pin "12") (pinfunction "GND12_12") (pintype "power_in"))
      (node (ref "U3") (pin "14") (pinfunction "GND14_14") (pintype "power_in"))
      (node (ref "U3") (pin "26") (pinfunction "GND26_26") (pintype "power_in"))
      (node (ref "U3") (pin "30") (pinfunction "GND30_30") (pintype "power_in"))
      (node (ref "U3") (pin "37") (pinfunction "EGP37_37") (pintype "power_in"))
      (node (ref "U3") (pin "38") (pinfunction "EGP38_38") (pintype "power_in"))
      (node (ref "U3") (pin "39") (pinfunction "EGP39_39") (pintype "power_in"))
      (node (ref "U3") (pin "40") (pinfunction "EGP40_40") (pintype "power_in"))
      (node (ref "U3") (pin "41") (pinfunction "EGP41_41") (pintype "power_in"))
      (node (ref "U3") (pin "42") (pinfunction "EGP42_42") (pintype "power_in"))
      (node (ref "U3") (pin "43") (pinfunction "EGP43_43") (pintype "power_in"))
      (node (ref "U3") (pin "44") (pinfunction "EGP44_44") (pintype "power_in"))
      (node (ref "U3") (pin "45") (pinfunction "EGP45_45") (pintype "power_in"))
      (node (ref "U3") (pin "46") (pinfunction "EGP46_46") (pintype "power_in"))
      (node (ref "U3") (pin "47") (pinfunction "EGP47_47") (pintype "power_in"))
      (node (ref "U3") (pin "48") (pinfunction "EGP48_48") (pintype "power_in"))
      (node (ref "U3") (pin "6") (pinfunction "GND6_6") (pintype "power_in"))
      (node (ref "U3") (pin "EG") (pinfunction "EGP156_EG") (pintype "power_in"))
      (node (ref "U34") (pin "2") (pinfunction "GND_2") (pintype "power_in"))
    )
    (net (code "34") (name "Net-(D4-A)") (class "Default")
      (node (ref "D4") (pin "2") (pinfunction "A_2") (pintype "passive"))
      (node (ref "R10") (pin "1") (pinfunction "1_1") (pintype "passive"))
    )
    (net (code "35") (name "Net-(D5-Anode)") (class "Default")
      (node (ref "D5") (pin "A") (pinfunction "Anode_A") (pintype "passive"))
      (node (ref "R11") (pin "1") (pinfunction "1_1") (pintype "passive"))
    )
    (net (code "36") (name "Net-(D6-Anode)") (class "Default")
      (node (ref "D6") (pin "A") (pinfunction "Anode_A") (pintype "passive"))
      (node (ref "R12") (pin "1") (pinfunction "1_1") (pintype "passive"))
    )
    (net (code "37") (name "Net-(D8-Anode)") (class "Default")
      (node (ref "D8") (pin "A") (pinfunction "Anode_A") (pintype "passive"))
      (node (ref "R22") (pin "1") (pinfunction "1_1") (pintype "passive"))
    )
    (net (code "38") (name "Net-(NC3-Pad2)") (class "Default")
      (node (ref "NC3") (pin "2") (pinfunction "2_2") (pintype "passive"))
      (node (ref "R22") (pin "2") (pinfunction "2_2") (pintype "passive"))
    )
    (net (code "39") (name "Net-(Q1A-D1)") (class "Default")
      (node (ref "BTN4") (pin "1") (pinfunction "1_1") (pintype "passive"))
      (node (ref "D2") (pin "1") (pintype "passive"))
      (node (ref "Q1") (pin "6") (pinfunction "D1_6") (pintype "passive"))
      (node (ref "R14") (pin "1") (pinfunction "1_1") (pintype "passive"))
      (node (ref "U3") (pin "7") (pinfunction "GREEN/SWITCH_1_7") (pintype "bidirectional"))
    )
    (net (code "40") (name "Net-(Q1B-D2)") (class "Default")
      (node (ref "BTN5") (pin "1") (pinfunction "1_1") (pintype "passive"))
      (node (ref "D3") (pin "1") (pintype "passive"))
      (node (ref "Q1") (pin "3") (pinfunction "D2_3") (pintype "passive"))
      (node (ref "U3") (pin "18") (pinfunction "SWITCH_2/RMII_CRSDV_18") (pintype "input"))
    )
    (net (code "41") (name "Net-(Q2A-D1)") (class "Default")
      (node (ref "Q2") (pin "3") (pinfunction "D2_3") (pintype "passive"))
      (node (ref "Q2") (pin "6") (pinfunction "D1_6") (pintype "passive"))
      (node (ref "U3") (pin "19") (pinfunction "RESET_N_19") (pintype "input"))
    )
    (net (code "42") (name "Net-(Q2B-G2)") (class "Default")
      (node (ref "NC1") (pin "1") (pinfunction "1_1") (pintype "passive"))
      (node (ref "Q2") (pin "5") (pinfunction "G2_5") (pintype "passive"))
    )
    (net (code "43") (name "Net-(Q3A-D1)") (class "Default")
      (node (ref "Q3") (pin "6") (pinfunction "D1_6") (pintype "passive"))
      (node (ref "R12") (pin "2") (pinfunction "2_2") (pintype "passive"))
    )
    (net (code "44") (name "Net-(Q3B-D2)") (class "Default")
      (node (ref "Q3") (pin "3") (pinfunction "D2_3") (pintype "passive"))
      (node (ref "R11") (pin "2") (pinfunction "2_2") (pintype "passive"))
    )
    (net (code "45") (name "Net-(RGB1-B)") (class "Default")
      (node (ref "R15") (pin "2") (pinfunction "2_2") (pintype "passive"))
      (node (ref "RGB1") (pin "3") (pinfunction "B_3") (pintype "passive"))
    )
    (net (code "46") (name "Net-(RGB1-G)") (class "Default")
      (node (ref "R14") (pin "2") (pinfunction "2_2") (pintype "passive"))
      (node (ref "RGB1") (pin "2") (pinfunction "G_2") (pintype "passive"))
    )
    (net (code "47") (name "Net-(RGB1-R)") (class "Default")
      (node (ref "R13") (pin "2") (pinfunction "2_2") (pintype "passive"))
      (node (ref "RGB1") (pin "1") (pinfunction "R_1") (pintype "passive"))
    )
    (net (code "48") (name "Net-(U3-BLUE{slash}RMII_TXEN)") (class "Default")
      (node (ref "R15") (pin "1") (pinfunction "1_1") (pintype "passive"))
      (node (ref "U3") (pin "8") (pinfunction "BLUE/RMII_TXEN_8") (pintype "output"))
    )
    (net (code "49") (name "Net-(U3-RED)") (class "Default")
      (node (ref "R13") (pin "1") (pinfunction "1_1") (pintype "passive"))
      (node (ref "U3") (pin "1") (pinfunction "RED_1") (pintype "output"))
    )
    (net (code "50") (name "Net-(U3-RMII_CLK)") (class "Default")
      (node (ref "TP9") (pin "1") (pintype "passive"))
      (node (ref "U3") (pin "27") (pinfunction "RMII_CLK_27") (pintype "input"))
    )
    (net (code "51") (name "Net-(U3-VCC)") (class "Default")
      (node (ref "C16") (pin "1") (pinfunction "1_1") (pintype "passive"))
      (node (ref "C17") (pin "2") (pinfunction "2_2") (pintype "passive"))
      (node (ref "C28") (pin "1") (pinfunction "1_1") (pintype "passive"))
      (node (ref "J2") (pin "2") (pinfunction "2_2") (pintype "passive"))
      (node (ref "NC5") (pin "1") (pinfunction "1_1") (pintype "passive"))
      (node (ref "U3") (pin "10") (pinfunction "VCC_10") (pintype "power_in"))
      (node (ref "U3") (pin "9") (pinfunction "VCC_IO_9") (pintype "power_in"))
    )
    (net (code "52") (name "Net-(U34-FLAGB)") (class "Default")
      (node (ref "R33") (pin "2") (pinfunction "2_2") (pintype "passive"))
      (node (ref "U34") (pin "4") (pinfunction "FLAGB_4") (pintype "output"))
    )
    (net (code "53") (name "VCC_NINA") (class "Default")
      (node (ref "C35") (pin "1") (pinfunction "1_1") (pintype "passive"))
      (node (ref "C59") (pin "1") (pinfunction "1_1") (pintype "passive"))
      (node (ref "C60") (pin "1") (pinfunction "1_1") (pintype "passive"))
      (node (ref "C64") (pin "1") (pinfunction "1_1") (pintype "passive"))
      (node (ref "C67") (pin "1") (pinfunction "1_1") (pintype "passive"))
      (node (ref "C95") (pin "1") (pinfunction "1_1") (pintype "passive"))
      (node (ref "J2") (pin "3") (pinfunction "3_3") (pintype "passive"))
      (node (ref "NC3") (pin "1") (pinfunction "1_1") (pintype "passive"))
      (node (ref "NC5") (pin "2") (pinfunction "2_2") (pintype "passive"))
      (node (ref "Q3") (pin "1") (pinfunction "S1_1") (pintype "passive"))
      (node (ref "Q3") (pin "4") (pinfunction "S2_4") (pintype "passive"))
      (node (ref "R10") (pin "2") (pinfunction "2_2") (pintype "passive"))
      (node (ref "R33") (pin "1") (pinfunction "1_1") (pintype "passive"))
      (node (ref "R48") (pin "1") (pinfunction "1_1") (pintype "passive"))
      (node (ref "R51") (pin "1") (pinfunction "1_1") (pintype "passive"))
      (node (ref "R52") (pin "1") (pinfunction "1_1") (pintype "passive"))
      (node (ref "RGB1") (pin "4") (pinfunction "A_4") (pintype "passive"))
      (node (ref "TP12") (pin "1") (pintype "passive"))
      (node (ref "U12") (pin "1") (pinfunction "VCCA_1") (pintype "power_in"))
      (node (ref "U12") (pin "15") (pinfunction "DIR2_15") (pintype "input"))
      (node (ref "U12") (pin "7") (pinfunction "DIR4_7") (pintype "input"))
      (node (ref "U14") (pin "C1") (pinfunction "VCC(A)_C1") (pintype "power_in"))
      (node (ref "U15") (pin "1") (pinfunction "VCCA_1") (pintype "power_in"))
      (node (ref "U15") (pin "10") (pinfunction "DIR3_10") (pintype "input"))
      (node (ref "U15") (pin "2") (pinfunction "DIR1_2") (pintype "input"))
      (node (ref "U16") (pin "C1") (pinfunction "VCC(A)_C1") (pintype "power_in"))
      (node (ref "U34") (pin "5") (pinfunction "VOUT_5") (pintype "power_in"))
    )
    (net (code "54") (name "VDD_NORA") (class "Default")
      (node (ref "C68") (pin "2") (pinfunction "2_2") (pintype "passive"))
      (node (ref "R63") (pin "1") (pinfunction "1_1") (pintype "passive"))
      (node (ref "U16") (pin "B2") (pinfunction "VCC(B)_B2") (pintype "power_in"))
    )
    (net (code "55") (name "unconnected-(U3-ANT-Pad13)") (class "Default")
      (node (ref "U3") (pin "13") (pinfunction "ANT_13") (pintype "bidirectional+no_connect"))
    )
    (net (code "56") (name "unconnected-(U3-LOG_BOOT-Pad32)") (class "Default")
      (node (ref "U3") (pin "32") (pinfunction "LOG_BOOT_32") (pintype "input+no_connect"))
    )
    (net (code "57") (name "unconnected-(U3-LPO_IN-Pad5)") (class "Default")
      (node (ref "U3") (pin "5") (pinfunction "LPO_IN_5") (pintype "input+no_connect"))
    )
    (net (code "58") (name "unconnected-(U3-RMII_MDCLK-Pad25)") (class "Default")
      (node (ref "U3") (pin "25") (pinfunction "RMII_MDCLK_25") (pintype "output+no_connect"))
    )
    (net (code "59") (name "unconnected-(U3-RMII_MDIO-Pad24)") (class "Default")
      (node (ref "U3") (pin "24") (pinfunction "RMII_MDIO_24") (pintype "bidirectional+no_connect"))
    )
    (net (code "60") (name "unconnected-(U3-RSVD2-Pad2)") (class "Default")
      (node (ref "U3") (pin "2") (pinfunction "RSVD2_2") (pintype "passive+no_connect"))
    )
    (net (code "61") (name "unconnected-(U3-RSVD3-Pad3)") (class "Default")
      (node (ref "U3") (pin "3") (pinfunction "RSVD3_3") (pintype "passive+no_connect"))
    )
    (net (code "62") (name "unconnected-(U3-RSVD4-Pad4)") (class "Default")
      (node (ref "U3") (pin "4") (pinfunction "RSVD4_4") (pintype "passive+no_connect"))
    )
    (net (code "63") (name "unconnected-(U3-RSVD11-Pad11)") (class "Default")
      (node (ref "U3") (pin "11") (pinfunction "RSVD11_11") (pintype "passive+no_connect"))
    )
    (net (code "64") (name "unconnected-(U3-RSVD15-Pad15)") (class "Default")
      (node (ref "U3") (pin "15") (pinfunction "RSVD15_15") (pintype "passive+no_connect"))
    )
    (net (code "65") (name "unconnected-(U3-RSVD28-Pad28)") (class "Default")
      (node (ref "U3") (pin "28") (pinfunction "RSVD28_28") (pintype "passive+no_connect"))
    )
    (net (code "66") (name "unconnected-(U3-RSVD29-Pad29)") (class "Default")
      (node (ref "U3") (pin "29") (pinfunction "RSVD29_29") (pintype "passive+no_connect"))
    )
    (net (code "67") (name "unconnected-(U3-RSVD31-Pad31)") (class "Default")
      (node (ref "U3") (pin "31") (pinfunction "RSVD31_31") (pintype "passive+no_connect"))
    )
    (net (code "68") (name "unconnected-(U3-RSVD33-Pad33)") (class "Default")
      (node (ref "U3") (pin "33") (pinfunction "RSVD33_33") (pintype "passive+no_connect"))
    )
    (net (code "69") (name "unconnected-(U3-RSVD34-Pad34)") (class "Default")
      (node (ref "U3") (pin "34") (pinfunction "RSVD34_34") (pintype "passive+no_connect"))
    )
    (net (code "70") (name "unconnected-(U3-RSVD35-Pad35)") (class "Default")
      (node (ref "U3") (pin "35") (pinfunction "RSVD35_35") (pintype "passive+no_connect"))
    )
    (net (code "71") (name "unconnected-(U3-RSVD36-Pad36)") (class "Default")
      (node (ref "U3") (pin "36") (pinfunction "RSVD36_36") (pintype "passive+no_connect"))
    )
  )
)
